# BLL-EBOOK.net
KiCad netlist of a schematic drawn in EAGLE
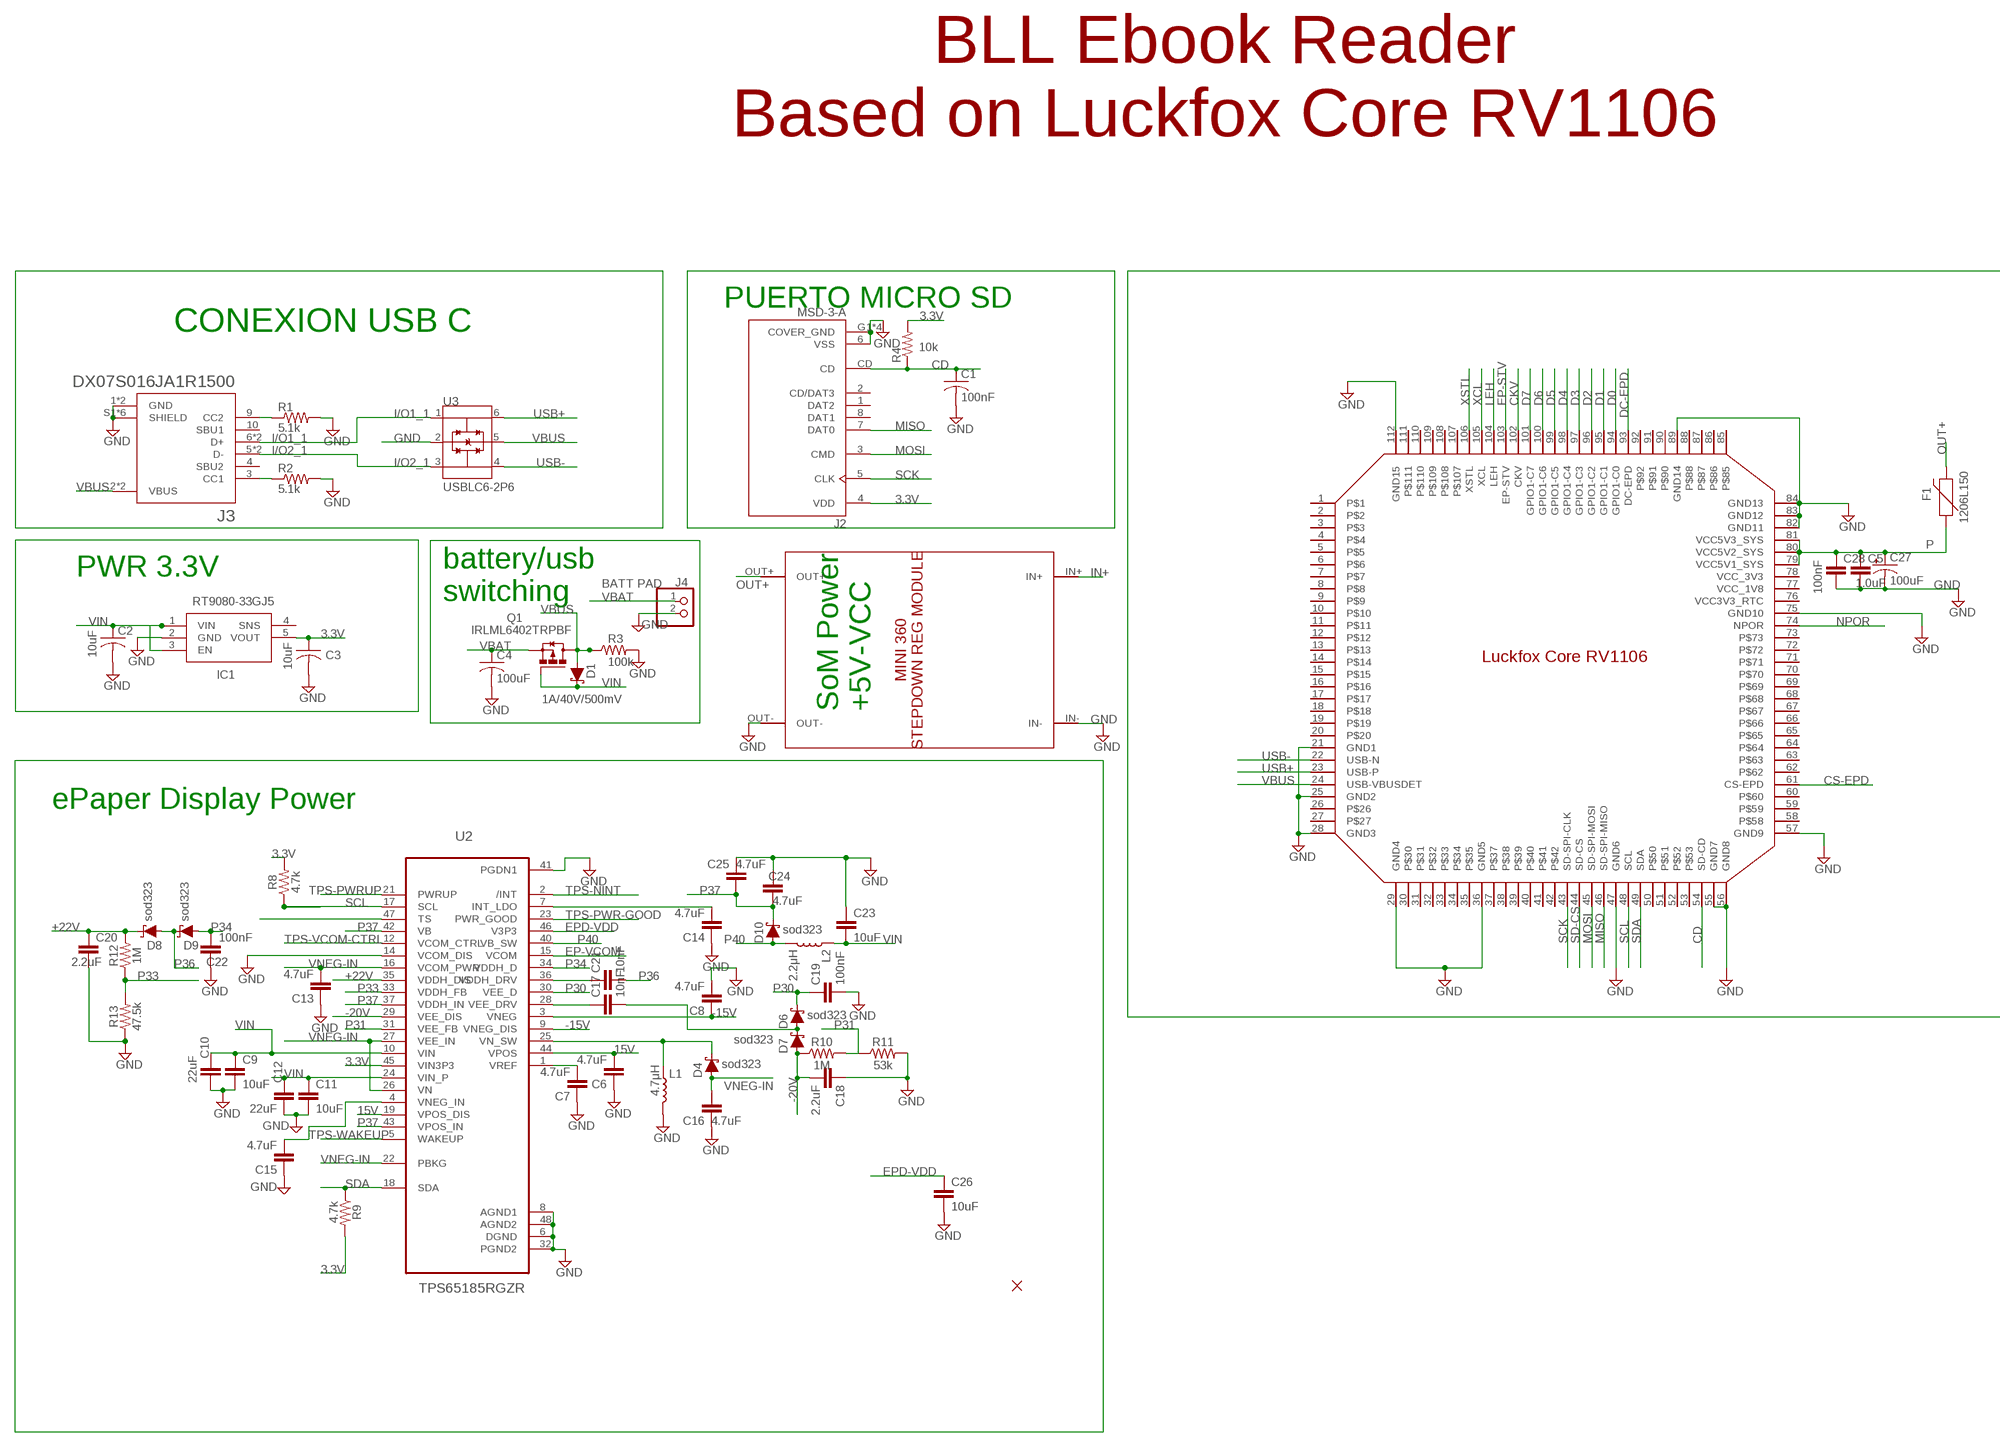
[diagram p0: schematic, sheet 1, part 1 of 2]
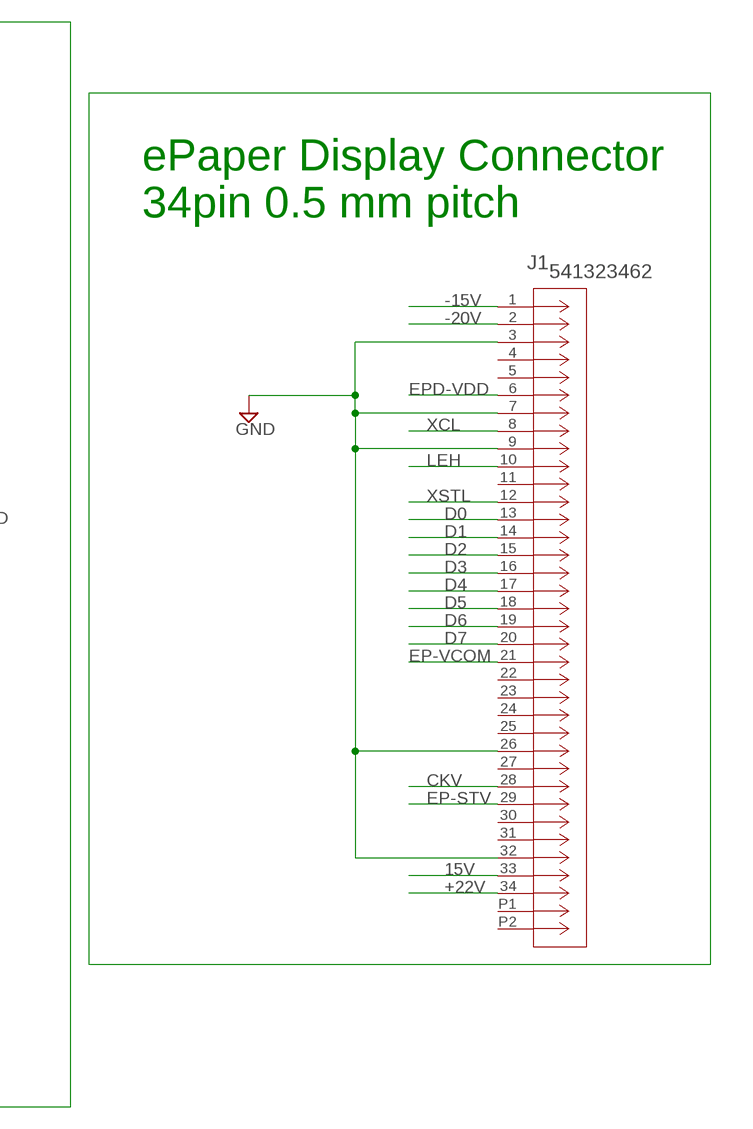
[diagram p1: schematic, sheet 1, part 2 of 2]

(export (version "E")
  (design (tool "Eeschema 10.0.6"))
  (components
    (comp (ref "C1")
      (value "100nF")
      (footprint "eagle-import:C0603")
      (libsource (lib "eagle-import") (part "C-USC0603"))
    )
    (comp (ref "C2")
      (value "10uF")
      (footprint "eagle-import:C0603")
      (libsource (lib "eagle-import") (part "C-USC0603"))
    )
    (comp (ref "C3")
      (value "10uF")
      (footprint "eagle-import:C0603")
      (libsource (lib "eagle-import") (part "C-USC0603"))
    )
    (comp (ref "C4")
      (value "100uF")
      (footprint "eagle-import:C0603")
      (libsource (lib "eagle-import") (part "C-USC0603"))
    )
    (comp (ref "C5")
      (value "1.0uF")
      (footprint "eagle-import:0603")
      (libsource (lib "eagle-import") (part "1.0UF-0603-16V-10%-X7R"))
    )
    (comp (ref "C6")
      (value "4.7uF")
      (footprint "eagle-import:0603")
      (libsource (lib "eagle-import") (part "4.7UF-0603-35V-(20%)"))
    )
    (comp (ref "C7")
      (value "4.7uF")
      (footprint "eagle-import:0603")
      (libsource (lib "eagle-import") (part "4.7UF-0603-35V-(20%)"))
    )
    (comp (ref "C8")
      (value "4.7uF")
      (footprint "eagle-import:0603")
      (libsource (lib "eagle-import") (part "4.7UF-0603-35V-(20%)"))
    )
    (comp (ref "C9")
      (value "10uF")
      (footprint "eagle-import:0805")
      (libsource (lib "eagle-import") (part "10UF-0805-10V-10%"))
    )
    (comp (ref "C10")
      (value "22uF")
      (footprint "eagle-import:0805")
      (libsource (lib "eagle-import") (part "22UF-0805-16V-20%"))
    )
    (comp (ref "C11")
      (value "10uF")
      (footprint "eagle-import:0805")
      (libsource (lib "eagle-import") (part "10UF-0805-10V-10%"))
    )
    (comp (ref "C12")
      (value "22uF")
      (footprint "eagle-import:0805")
      (libsource (lib "eagle-import") (part "22UF-0805-16V-20%"))
    )
    (comp (ref "C13")
      (value "4.7uF")
      (footprint "eagle-import:0603")
      (libsource (lib "eagle-import") (part "4.7UF-0603-35V-(20%)"))
    )
    (comp (ref "C14")
      (value "4.7uF")
      (footprint "eagle-import:0603")
      (libsource (lib "eagle-import") (part "4.7UF-0603-35V-(20%)"))
    )
    (comp (ref "C15")
      (value "4.7uF")
      (footprint "eagle-import:0603")
      (libsource (lib "eagle-import") (part "4.7UF-0603-35V-(20%)"))
    )
    (comp (ref "C16")
      (value "4.7uF")
      (footprint "eagle-import:0603")
      (libsource (lib "eagle-import") (part "4.7UF-0603-35V-(20%)"))
    )
    (comp (ref "C17")
      (value "10nF")
      (footprint "eagle-import:0603")
      (libsource (lib "eagle-import") (part "10NF-0603-50V-10%"))
    )
    (comp (ref "C18")
      (value "2.2uF")
      (footprint "eagle-import:1206")
      (libsource (lib "eagle-import") (part "2.2UF-1206-50V-10%"))
    )
    (comp (ref "C19")
      (value "100nF")
      (footprint "eagle-import:0603")
      (libsource (lib "eagle-import") (part "DNP-0603"))
    )
    (comp (ref "C20")
      (value "2.2uF")
      (footprint "eagle-import:1206")
      (libsource (lib "eagle-import") (part "2.2UF-1206-50V-10%"))
    )
    (comp (ref "C21")
      (value "10nF")
      (footprint "eagle-import:0603")
      (libsource (lib "eagle-import") (part "10NF-0603-50V-10%"))
    )
    (comp (ref "C22")
      (value "100nF")
      (footprint "eagle-import:0603")
      (libsource (lib "eagle-import") (part "DNP-0603"))
    )
    (comp (ref "C23")
      (value "10uF")
      (footprint "eagle-import:0805")
      (libsource (lib "eagle-import") (part "10UF-0805-10V-10%"))
    )
    (comp (ref "C24")
      (value "4.7uF")
      (footprint "eagle-import:0603")
      (libsource (lib "eagle-import") (part "4.7UF-0603-35V-(20%)"))
    )
    (comp (ref "C25")
      (value "4.7uF")
      (footprint "eagle-import:0603")
      (libsource (lib "eagle-import") (part "4.7UF-0603-35V-(20%)"))
    )
    (comp (ref "C26")
      (value "10uF")
      (footprint "eagle-import:0805")
      (libsource (lib "eagle-import") (part "10UF-0805-10V-10%"))
    )
    (comp (ref "C27")
      (value "100uF")
      (footprint "eagle-import:EIA3528")
      (libsource (lib "eagle-import") (part "100UF-POLAR-EIA3528-10V-20%(TANT)"))
    )
    (comp (ref "C28")
      (value "100nF")
      (footprint "eagle-import:0805")
      (libsource (lib "eagle-import") (part "CAP-0805"))
    )
    (comp (ref "D1")
      (value "1A/40V/500mV")
      (footprint "eagle-import:SMA-DIODE")
      (libsource (lib "eagle-import") (part "DIODE-SCHOTTKY-SS14"))
    )
    (comp (ref "D4")
      (value "sod323")
      (footprint "eagle-import:SOD-323")
      (libsource (lib "eagle-import") (part "DIODE-SCHOTTKY-PMEG4005EJ"))
    )
    (comp (ref "D6")
      (value "sod323")
      (footprint "eagle-import:SOD-323")
      (libsource (lib "eagle-import") (part "DIODE-SCHOTTKY-PMEG4005EJ"))
    )
    (comp (ref "D7")
      (value "sod323")
      (footprint "eagle-import:SOD-323")
      (libsource (lib "eagle-import") (part "DIODE-SCHOTTKY-PMEG4005EJ"))
    )
    (comp (ref "D8")
      (value "sod323")
      (footprint "eagle-import:SOD-323")
      (libsource (lib "eagle-import") (part "DIODE-SCHOTTKY-PMEG4005EJ"))
    )
    (comp (ref "D9")
      (value "sod323")
      (footprint "eagle-import:SOD-323")
      (libsource (lib "eagle-import") (part "DIODE-SCHOTTKY-PMEG4005EJ"))
    )
    (comp (ref "D10")
      (value "sod323")
      (footprint "eagle-import:SOD-323")
      (libsource (lib "eagle-import") (part "DIODE-SCHOTTKY-PMEG4005EJ"))
    )
    (comp (ref "F1")
      (value "1206L150")
      (footprint "eagle-import:1206")
      (libsource (lib "eagle-import") (part "PPTC_6V500MA-2"))
    )
    (comp (ref "IC1")
      (value "RT9080-33GJ5")
      (footprint "eagle-import:SOT94P280X100-5N")
      (fields (field (name "MF") "Richtek USA"))
      (libsource (lib "eagle-import") (part "RT9080-33GJ5"))
    )
    (comp (ref "J1")
      (value "541323462")
      (footprint "eagle-import:CON_541323462_MOL")
      (fields (field (name "MF") "Molex"))
      (libsource (lib "eagle-import") (part "541323462"))
    )
    (comp (ref "J2")
      (value "MSD-3-A")
      (footprint "eagle-import:CUI_MSD-3-A")
      (fields (field (name "MF") "Same Sky"))
      (libsource (lib "eagle-import") (part "MSD-3-A"))
    )
    (comp (ref "J3")
      (value "DX07S016JA1R1500")
      (footprint "eagle-import:JAE_DX07S016JA1R1500")
      (fields (field (name "MF") "JAE Electronics"))
      (libsource (lib "eagle-import") (part "DX07S016JA1R1500"))
    )
    (comp (ref "J4")
      (value "BATT PAD")
      (footprint "eagle-import:1X02_90")
      (libsource (lib "eagle-import") (part "PINHD-1X2/90"))
    )
    (comp (ref "L1")
      (value "4.7μH")
      (footprint "eagle-import:1008(2520)")
      (libsource (lib "eagle-import") (part "4.7μH_SHIELDED_INDUCTOR"))
    )
    (comp (ref "L2")
      (value "2.2μH")
      (footprint "eagle-import:0806")
      (libsource (lib "eagle-import") (part "2.2μH_SHIELDED_INDUCTOR"))
    )
    (comp (ref "Q1")
      (value "IRLML6402TRPBF")
      (footprint "eagle-import:SOT23")
      (fields (field (name "MF") "Infineon Technologies") (field (name "MP") "IRLML6402"))
      (libsource (lib "eagle-import") (part "IRLML6402TRPBF"))
    )
    (comp (ref "R1")
      (value "5.1k")
      (footprint "eagle-import:M0805")
      (libsource (lib "eagle-import") (part "R-US_M0805"))
    )
    (comp (ref "R2")
      (value "5.1k")
      (footprint "eagle-import:M0805")
      (libsource (lib "eagle-import") (part "R-US_M0805"))
    )
    (comp (ref "R3")
      (value "100k")
      (footprint "eagle-import:R0603")
      (libsource (lib "eagle-import") (part "R-US_R0603"))
    )
    (comp (ref "R4")
      (value "10k")
      (footprint "eagle-import:M0805")
      (libsource (lib "eagle-import") (part "R-US_M0805"))
    )
    (comp (ref "R8")
      (value "4.7k")
      (footprint "eagle-import:0603")
      (libsource (lib "eagle-import") (part "4.7KOHM-0603-1/10W-1%"))
    )
    (comp (ref "R9")
      (value "4.7k")
      (footprint "eagle-import:0603")
      (libsource (lib "eagle-import") (part "4.7KOHM-0603-1/10W-1%"))
    )
    (comp (ref "R10")
      (value "1M")
      (footprint "eagle-import:0603")
      (libsource (lib "eagle-import") (part "1MOHM-0603-1/4W-5%"))
    )
    (comp (ref "R11")
      (value "53k")
      (footprint "eagle-import:0805")
      (libsource (lib "eagle-import") (part "RESISTOR0805"))
    )
    (comp (ref "R12")
      (value "1M")
      (footprint "eagle-import:0603")
      (libsource (lib "eagle-import") (part "1MOHM-0603-1/4W-5%"))
    )
    (comp (ref "R13")
      (value "47.5k")
      (footprint "eagle-import:0805")
      (libsource (lib "eagle-import") (part "RESISTOR0805"))
    )
    (comp (ref "U$1")
      (value "LUCKFOX_CORE_RV1106")
      (footprint "eagle-import:CORE1106-SMT")
      (fields (field (name "MF") "Luckfox Systems") (field (name "MP") "LuckFox Core1106"))
      (libsource (lib "eagle-import") (part "LUCKFOX_CORE_RV1106"))
    )
    (comp (ref "U$2")
      (value "MINI360-MOD-REG")
      (footprint "eagle-import:MINI360")
      (libsource (lib "eagle-import") (part "MINI360-MOD-REG"))
    )
    (comp (ref "U2")
      (value "TPS65185RGZR")
      (footprint "eagle-import:QFN50P700X700X100-49N")
      (fields (field (name "MF") "Texas Instruments"))
      (libsource (lib "eagle-import") (part "TPS65185RGZR"))
    )
    (comp (ref "U3")
      (value "USBLC6-2P6")
      (footprint "eagle-import:SOT50P160X60-6N")
      (fields (field (name "MF") "STMicroelectronics"))
      (libsource (lib "eagle-import") (part "USBLC6-2P6"))
    )
  )
  (nets
    (net (code "1") (name "/+22V") (class "Default")
      (node (ref "C20") (pin "1") (pinfunction "1_1") (pintype "passive"))
      (node (ref "D8") (pin "C") (pinfunction "C_C") (pintype "passive"))
      (node (ref "J1") (pin "34") (pinfunction "34_34") (pintype "passive"))
      (node (ref "R12") (pin "2") (pinfunction "2_2") (pintype "passive"))
      (node (ref "U2") (pin "35") (pinfunction "VDDH_DIS_35") (pintype "input"))
    )
    (net (code "2") (name "/-15V") (class "Default")
      (node (ref "C8") (pin "1") (pinfunction "1_1") (pintype "passive"))
      (node (ref "J1") (pin "1") (pinfunction "1_1") (pintype "passive"))
      (node (ref "U2") (pin "3") (pinfunction "VNEG_3") (pintype "output"))
      (node (ref "U2") (pin "9") (pinfunction "VNEG_DIS_9") (pintype "output"))
    )
    (net (code "3") (name "/-20V") (class "Default")
      (node (ref "C18") (pin "2") (pinfunction "2_2") (pintype "passive"))
      (node (ref "D7") (pin "A") (pinfunction "A_A") (pintype "passive"))
      (node (ref "J1") (pin "2") (pinfunction "2_2") (pintype "passive"))
      (node (ref "R10") (pin "1") (pinfunction "1_1") (pintype "passive"))
      (node (ref "U2") (pin "29") (pinfunction "VEE_DIS_29") (pintype "input"))
    )
    (net (code "4") (name "/3.3V") (class "Default")
      (node (ref "C3") (pin "1") (pinfunction "1_1") (pintype "passive"))
      (node (ref "IC1") (pin "5") (pinfunction "VOUT_5") (pintype "bidirectional"))
      (node (ref "J2") (pin "4") (pinfunction "VDD_4") (pintype "power_in"))
      (node (ref "R4") (pin "2") (pinfunction "2_2") (pintype "passive"))
      (node (ref "R8") (pin "2") (pinfunction "2_2") (pintype "passive"))
      (node (ref "R9") (pin "2") (pinfunction "2_2") (pintype "passive"))
      (node (ref "U2") (pin "45") (pinfunction "VIN3P3_45") (pintype "input"))
    )
    (net (code "5") (name "/15V") (class "Default")
      (node (ref "C6") (pin "2") (pinfunction "2_2") (pintype "passive"))
      (node (ref "J1") (pin "33") (pinfunction "33_33") (pintype "passive"))
      (node (ref "U2") (pin "19") (pinfunction "VPOS_DIS_19") (pintype "input"))
      (node (ref "U2") (pin "44") (pinfunction "VPOS_44") (pintype "output"))
    )
    (net (code "6") (name "/CD") (class "Default")
      (node (ref "C1") (pin "1") (pinfunction "1_1") (pintype "passive"))
      (node (ref "J2") (pin "CD") (pinfunction "CD_CD") (pintype "passive"))
      (node (ref "R4") (pin "1") (pinfunction "1_1") (pintype "passive"))
      (node (ref "U$1") (pin "54") (pinfunction "SD-CD_54") (pintype "bidirectional"))
    )
    (net (code "7") (name "/CKV") (class "Default")
      (node (ref "J1") (pin "28") (pinfunction "28_28") (pintype "passive"))
      (node (ref "U$1") (pin "102") (pinfunction "CKV_102") (pintype "bidirectional"))
    )
    (net (code "8") (name "/CS-EPD") (class "Default")
      (node (ref "U$1") (pin "61") (pinfunction "CS-EPD_61") (pintype "bidirectional"))
    )
    (net (code "9") (name "/D0") (class "Default")
      (node (ref "J1") (pin "13") (pinfunction "13_13") (pintype "passive"))
      (node (ref "U$1") (pin "94") (pinfunction "GPIO1-C0_94") (pintype "bidirectional"))
    )
    (net (code "10") (name "/D1") (class "Default")
      (node (ref "J1") (pin "14") (pinfunction "14_14") (pintype "passive"))
      (node (ref "U$1") (pin "95") (pinfunction "GPIO1-C1_95") (pintype "bidirectional"))
    )
    (net (code "11") (name "/D2") (class "Default")
      (node (ref "J1") (pin "15") (pinfunction "15_15") (pintype "passive"))
      (node (ref "U$1") (pin "96") (pinfunction "GPIO1-C2_96") (pintype "bidirectional"))
    )
    (net (code "12") (name "/D3") (class "Default")
      (node (ref "J1") (pin "16") (pinfunction "16_16") (pintype "passive"))
      (node (ref "U$1") (pin "97") (pinfunction "GPIO1-C3_97") (pintype "bidirectional"))
    )
    (net (code "13") (name "/D4") (class "Default")
      (node (ref "J1") (pin "17") (pinfunction "17_17") (pintype "passive"))
      (node (ref "U$1") (pin "98") (pinfunction "GPIO1-C4_98") (pintype "bidirectional"))
    )
    (net (code "14") (name "/D5") (class "Default")
      (node (ref "J1") (pin "18") (pinfunction "18_18") (pintype "passive"))
      (node (ref "U$1") (pin "99") (pinfunction "GPIO1-C5_99") (pintype "bidirectional"))
    )
    (net (code "15") (name "/D6") (class "Default")
      (node (ref "J1") (pin "19") (pinfunction "19_19") (pintype "passive"))
      (node (ref "U$1") (pin "100") (pinfunction "GPIO1-C6_100") (pintype "bidirectional"))
    )
    (net (code "16") (name "/D7") (class "Default")
      (node (ref "J1") (pin "20") (pinfunction "20_20") (pintype "passive"))
      (node (ref "U$1") (pin "101") (pinfunction "GPIO1-C7_101") (pintype "bidirectional"))
    )
    (net (code "17") (name "/DC-EPD") (class "Default")
      (node (ref "U$1") (pin "93") (pinfunction "DC-EPD_93") (pintype "bidirectional"))
    )
    (net (code "18") (name "/EP-STV") (class "Default")
      (node (ref "J1") (pin "29") (pinfunction "29_29") (pintype "passive"))
      (node (ref "U$1") (pin "103") (pinfunction "EP-STV_103") (pintype "bidirectional"))
    )
    (net (code "19") (name "/EP-VCOM") (class "Default")
      (node (ref "J1") (pin "21") (pinfunction "21_21") (pintype "passive"))
      (node (ref "U2") (pin "15") (pinfunction "VCOM_15") (pintype "output"))
    )
    (net (code "20") (name "/EPD-VDD") (class "Default")
      (node (ref "C26") (pin "1") (pinfunction "1_1") (pintype "passive"))
      (node (ref "J1") (pin "6") (pinfunction "6_6") (pintype "passive"))
      (node (ref "U2") (pin "46") (pinfunction "V3P3_46") (pintype "output"))
    )
    (net (code "21") (name "/IN+") (class "Default")
      (node (ref "U$2") (pin "IN+") (pinfunction "IN+_IN+") (pintype "bidirectional"))
    )
    (net (code "22") (name "/I{slash}O1_1") (class "Default")
      (node (ref "J3") (pin "6") (pinfunction "D+_6") (pintype "passive"))
      (node (ref "J3") (pin "7") (pinfunction "D+_7") (pintype "passive"))
      (node (ref "U3") (pin "1") (pinfunction "I/O1_1_1") (pintype "bidirectional"))
    )
    (net (code "23") (name "/I{slash}O2_1") (class "Default")
      (node (ref "J3") (pin "5") (pinfunction "D-_5") (pintype "passive"))
      (node (ref "J3") (pin "8") (pinfunction "D-_8") (pintype "passive"))
      (node (ref "U3") (pin "3") (pinfunction "I/O2_1_3") (pintype "bidirectional"))
    )
    (net (code "24") (name "/LEH") (class "Default")
      (node (ref "J1") (pin "10") (pinfunction "10_10") (pintype "passive"))
      (node (ref "U$1") (pin "104") (pinfunction "LEH_104") (pintype "bidirectional"))
    )
    (net (code "25") (name "/MISO") (class "Default")
      (node (ref "J2") (pin "7") (pinfunction "DAT0_7") (pintype "bidirectional"))
      (node (ref "U$1") (pin "46") (pinfunction "SD-SPI-MISO_46") (pintype "bidirectional"))
    )
    (net (code "26") (name "/MOSI") (class "Default")
      (node (ref "J2") (pin "3") (pinfunction "CMD_3") (pintype "bidirectional"))
      (node (ref "U$1") (pin "45") (pinfunction "SD-SPI-MOSI_45") (pintype "bidirectional"))
    )
    (net (code "27") (name "/NPOR") (class "Default")
      (node (ref "U$1") (pin "74") (pinfunction "NPOR_74") (pintype "bidirectional"))
    )
    (net (code "28") (name "/OUT+") (class "Default")
      (node (ref "F1") (pin "2") (pinfunction "2_2") (pintype "bidirectional"))
      (node (ref "U$2") (pin "OUT+") (pinfunction "OUT+_OUT+") (pintype "bidirectional"))
    )
    (net (code "29") (name "/P") (class "Default")
      (node (ref "C27") (pin "A") (pinfunction "+_A") (pintype "passive"))
      (node (ref "C28") (pin "1") (pinfunction "1_1") (pintype "passive"))
      (node (ref "C5") (pin "1") (pinfunction "1_1") (pintype "passive"))
      (node (ref "F1") (pin "1") (pinfunction "1_1") (pintype "bidirectional"))
      (node (ref "U$1") (pin "79") (pinfunction "VCC5V1_SYS_79") (pintype "power_in"))
      (node (ref "U$1") (pin "80") (pinfunction "VCC5V2_SYS_80") (pintype "bidirectional"))
      (node (ref "U$1") (pin "81") (pinfunction "VCC5V3_SYS_81") (pintype "bidirectional"))
    )
    (net (code "30") (name "/P30") (class "Default")
      (node (ref "C19") (pin "1") (pinfunction "1_1") (pintype "passive"))
      (node (ref "D6") (pin "C") (pinfunction "C_C") (pintype "passive"))
      (node (ref "U2") (pin "30") (pinfunction "VEE_D_30") (pintype "output"))
    )
    (net (code "31") (name "/P31") (class "Default")
      (node (ref "R10") (pin "2") (pinfunction "2_2") (pintype "passive"))
      (node (ref "R11") (pin "1") (pinfunction "1_1") (pintype "passive"))
      (node (ref "U2") (pin "31") (pinfunction "VEE_FB_31") (pintype "input"))
    )
    (net (code "32") (name "/P33") (class "Default")
      (node (ref "R12") (pin "1") (pinfunction "1_1") (pintype "passive"))
      (node (ref "R13") (pin "2") (pinfunction "2_2") (pintype "passive"))
      (node (ref "U2") (pin "33") (pinfunction "VDDH_FB_33") (pintype "input"))
    )
    (net (code "33") (name "/P34") (class "Default")
      (node (ref "C22") (pin "2") (pinfunction "2_2") (pintype "passive"))
      (node (ref "D9") (pin "A") (pinfunction "A_A") (pintype "passive"))
      (node (ref "U2") (pin "34") (pinfunction "VDDH_D_34") (pintype "output"))
    )
    (net (code "34") (name "/P36") (class "Default")
      (node (ref "C21") (pin "2") (pinfunction "2_2") (pintype "passive"))
      (node (ref "D8") (pin "A") (pinfunction "A_A") (pintype "passive"))
      (node (ref "D9") (pin "C") (pinfunction "C_C") (pintype "passive"))
    )
    (net (code "35") (name "/P37") (class "Default")
      (node (ref "C24") (pin "1") (pinfunction "1_1") (pintype "passive"))
      (node (ref "C25") (pin "1") (pinfunction "1_1") (pintype "passive"))
      (node (ref "D10") (pin "C") (pinfunction "C_C") (pintype "passive"))
      (node (ref "U2") (pin "37") (pinfunction "VDDH_IN_37") (pintype "input"))
      (node (ref "U2") (pin "42") (pinfunction "VB_42") (pintype "input"))
      (node (ref "U2") (pin "43") (pinfunction "VPOS_IN_43") (pintype "input"))
    )
    (net (code "36") (name "/P40") (class "Default")
      (node (ref "D10") (pin "A") (pinfunction "A_A") (pintype "passive"))
      (node (ref "L2") (pin "2") (pinfunction "2_2") (pintype "passive"))
      (node (ref "U2") (pin "40") (pinfunction "VB_SW_40") (pintype "output"))
    )
    (net (code "37") (name "/SCK") (class "Default")
      (node (ref "J2") (pin "5") (pinfunction "CLK_5") (pintype "input"))
      (node (ref "U$1") (pin "43") (pinfunction "SD-SPI-CLK_43") (pintype "bidirectional"))
    )
    (net (code "38") (name "/SCL") (class "Default")
      (node (ref "R8") (pin "1") (pinfunction "1_1") (pintype "passive"))
      (node (ref "U$1") (pin "48") (pinfunction "SCL_48") (pintype "bidirectional"))
      (node (ref "U2") (pin "17") (pinfunction "SCL_17") (pintype "input"))
    )
    (net (code "39") (name "/SD-CS") (class "Default")
      (node (ref "U$1") (pin "44") (pinfunction "SD-CS_44") (pintype "bidirectional"))
    )
    (net (code "40") (name "/SDA") (class "Default")
      (node (ref "R9") (pin "1") (pinfunction "1_1") (pintype "passive"))
      (node (ref "U$1") (pin "49") (pinfunction "SDA_49") (pintype "bidirectional"))
      (node (ref "U2") (pin "18") (pinfunction "SDA_18") (pintype "bidirectional"))
    )
    (net (code "41") (name "/TPS-NINT") (class "Default")
      (node (ref "U2") (pin "2") (pinfunction "/INT_2") (pintype "output"))
    )
    (net (code "42") (name "/TPS-PWR-GOOD") (class "Default")
      (node (ref "U2") (pin "23") (pinfunction "PWR_GOOD_23") (pintype "output"))
    )
    (net (code "43") (name "/TPS-PWRUP") (class "Default")
      (node (ref "U2") (pin "21") (pinfunction "PWRUP_21") (pintype "input"))
    )
    (net (code "44") (name "/TPS-VCOM-CTRL") (class "Default")
      (node (ref "U2") (pin "12") (pinfunction "VCOM_CTRL_12") (pintype "input"))
    )
    (net (code "45") (name "/TPS-WAKEUP") (class "Default")
      (node (ref "U2") (pin "5") (pinfunction "WAKEUP_5") (pintype "input"))
    )
    (net (code "46") (name "/USB+") (class "Default")
      (node (ref "U$1") (pin "23") (pinfunction "USB-P_23") (pintype "bidirectional"))
      (node (ref "U3") (pin "6") (pinfunction "I/O1_2_6") (pintype "bidirectional"))
    )
    (net (code "47") (name "/USB-") (class "Default")
      (node (ref "U$1") (pin "22") (pinfunction "USB-N_22") (pintype "bidirectional"))
      (node (ref "U3") (pin "4") (pinfunction "I/O2_2_4") (pintype "bidirectional"))
    )
    (net (code "48") (name "/VBAT") (class "Default")
      (node (ref "C4") (pin "1") (pinfunction "1_1") (pintype "passive"))
      (node (ref "J4") (pin "1") (pinfunction "1_1") (pintype "passive"))
      (node (ref "Q1") (pin "2") (pinfunction "S_2") (pintype "passive"))
    )
    (net (code "49") (name "/VBUS") (class "Default")
      (node (ref "D1") (pin "A") (pinfunction "A_A") (pintype "passive"))
      (node (ref "J3") (pin "11") (pinfunction "VBUS_11") (pintype "power_in"))
      (node (ref "J3") (pin "2") (pinfunction "VBUS_2") (pintype "power_in"))
      (node (ref "Q1") (pin "3") (pinfunction "D_3") (pintype "passive"))
      (node (ref "R3") (pin "1") (pinfunction "1_1") (pintype "passive"))
      (node (ref "U$1") (pin "24") (pinfunction "USB-VBUSDET_24") (pintype "bidirectional"))
      (node (ref "U3") (pin "5") (pinfunction "VBUS_5") (pintype "power_in"))
    )
    (net (code "50") (name "/VCC3V3_RTC") (class "Default")
      (node (ref "U$1") (pin "76") (pinfunction "VCC3V3_RTC_76") (pintype "power_in"))
    )
    (net (code "51") (name "/VIN") (class "Default")
      (node (ref "C10") (pin "1") (pinfunction "1_1") (pintype "passive"))
      (node (ref "C11") (pin "1") (pinfunction "1_1") (pintype "passive"))
      (node (ref "C12") (pin "1") (pinfunction "1_1") (pintype "passive"))
      (node (ref "C2") (pin "1") (pinfunction "1_1") (pintype "passive"))
      (node (ref "C23") (pin "2") (pinfunction "2_2") (pintype "passive"))
      (node (ref "C9") (pin "1") (pinfunction "1_1") (pintype "passive"))
      (node (ref "D1") (pin "C") (pinfunction "C_C") (pintype "passive"))
      (node (ref "IC1") (pin "1") (pinfunction "VIN_1") (pintype "bidirectional"))
      (node (ref "IC1") (pin "3") (pinfunction "EN_3") (pintype "bidirectional"))
      (node (ref "L2") (pin "1") (pinfunction "1_1") (pintype "passive"))
      (node (ref "Q1") (pin "1") (pinfunction "G_1") (pintype "passive"))
      (node (ref "U2") (pin "10") (pinfunction "VIN_10") (pintype "input"))
      (node (ref "U2") (pin "24") (pinfunction "VIN_P_24") (pintype "input"))
    )
    (net (code "52") (name "/VNEG-IN") (class "Default")
      (node (ref "C13") (pin "2") (pinfunction "2_2") (pintype "passive"))
      (node (ref "C16") (pin "2") (pinfunction "2_2") (pintype "passive"))
      (node (ref "D4") (pin "A") (pinfunction "A_A") (pintype "passive"))
      (node (ref "U2") (pin "16") (pinfunction "VCOM_PWR_16") (pintype "input"))
      (node (ref "U2") (pin "22") (pinfunction "PBKG_22") (pintype "bidirectional"))
      (node (ref "U2") (pin "26") (pinfunction "VN_26") (pintype "input"))
      (node (ref "U2") (pin "27") (pinfunction "VEE_IN_27") (pintype "input"))
    )
    (net (code "53") (name "/XCL") (class "Default")
      (node (ref "J1") (pin "8") (pinfunction "8_8") (pintype "passive"))
      (node (ref "U$1") (pin "105") (pinfunction "XCL_105") (pintype "bidirectional"))
    )
    (net (code "54") (name "/XSTL") (class "Default")
      (node (ref "J1") (pin "12") (pinfunction "12_12") (pintype "passive"))
      (node (ref "U$1") (pin "106") (pinfunction "XSTL_106") (pintype "bidirectional"))
    )
    (net (code "55") (name "GND") (class "Default")
      (node (ref "C1") (pin "2") (pinfunction "2_2") (pintype "passive"))
      (node (ref "C10") (pin "2") (pinfunction "2_2") (pintype "passive"))
      (node (ref "C11") (pin "2") (pinfunction "2_2") (pintype "passive"))
      (node (ref "C12") (pin "2") (pinfunction "2_2") (pintype "passive"))
      (node (ref "C13") (pin "1") (pinfunction "1_1") (pintype "passive"))
      (node (ref "C14") (pin "1") (pinfunction "1_1") (pintype "passive"))
      (node (ref "C15") (pin "1") (pinfunction "1_1") (pintype "passive"))
      (node (ref "C16") (pin "1") (pinfunction "1_1") (pintype "passive"))
      (node (ref "C18") (pin "1") (pinfunction "1_1") (pintype "passive"))
      (node (ref "C19") (pin "2") (pinfunction "2_2") (pintype "passive"))
      (node (ref "C2") (pin "2") (pinfunction "2_2") (pintype "passive"))
      (node (ref "C20") (pin "2") (pinfunction "2_2") (pintype "passive"))
      (node (ref "C22") (pin "1") (pinfunction "1_1") (pintype "passive"))
      (node (ref "C23") (pin "1") (pinfunction "1_1") (pintype "passive"))
      (node (ref "C24") (pin "2") (pinfunction "2_2") (pintype "passive"))
      (node (ref "C25") (pin "2") (pinfunction "2_2") (pintype "passive"))
      (node (ref "C26") (pin "2") (pinfunction "2_2") (pintype "passive"))
      (node (ref "C27") (pin "C") (pinfunction "-_C") (pintype "passive"))
      (node (ref "C28") (pin "2") (pinfunction "2_2") (pintype "passive"))
      (node (ref "C3") (pin "2") (pinfunction "2_2") (pintype "passive"))
      (node (ref "C4") (pin "2") (pinfunction "2_2") (pintype "passive"))
      (node (ref "C5") (pin "2") (pinfunction "2_2") (pintype "passive"))
      (node (ref "C6") (pin "1") (pinfunction "1_1") (pintype "passive"))
      (node (ref "C7") (pin "1") (pinfunction "1_1") (pintype "passive"))
      (node (ref "C8") (pin "2") (pinfunction "2_2") (pintype "passive"))
      (node (ref "C9") (pin "2") (pinfunction "2_2") (pintype "passive"))
      (node (ref "IC1") (pin "2") (pinfunction "GND_2") (pintype "bidirectional"))
      (node (ref "J1") (pin "26") (pinfunction "26_26") (pintype "passive"))
      (node (ref "J1") (pin "3") (pinfunction "3_3") (pintype "passive"))
      (node (ref "J1") (pin "32") (pinfunction "32_32") (pintype "passive"))
      (node (ref "J1") (pin "7") (pinfunction "7_7") (pintype "passive"))
      (node (ref "J1") (pin "9") (pinfunction "9_9") (pintype "passive"))
      (node (ref "J2") (pin "6") (pinfunction "VSS_6") (pintype "power_in"))
      (node (ref "J2") (pin "G1") (pinfunction "COVER_GND_G1") (pintype "power_in"))
      (node (ref "J2") (pin "G2") (pinfunction "COVER_GND_G2") (pintype "power_in"))
      (node (ref "J2") (pin "G3") (pinfunction "COVER_GND_G3") (pintype "power_in"))
      (node (ref "J2") (pin "G4") (pinfunction "COVER_GND_G4") (pintype "power_in"))
      (node (ref "J3") (pin "1") (pinfunction "GND_1") (pintype "power_in"))
      (node (ref "J3") (pin "12") (pinfunction "GND_12") (pintype "power_in"))
      (node (ref "J3") (pin "S1") (pinfunction "SHIELD_S1") (pintype "passive"))
      (node (ref "J3") (pin "S2") (pinfunction "SHIELD_S2") (pintype "passive"))
      (node (ref "J3") (pin "S3") (pinfunction "SHIELD_S3") (pintype "passive"))
      (node (ref "J3") (pin "S4") (pinfunction "SHIELD_S4") (pintype "passive"))
      (node (ref "J3") (pin "S5") (pinfunction "SHIELD_S5") (pintype "passive"))
      (node (ref "J3") (pin "S6") (pinfunction "SHIELD_S6") (pintype "passive"))
      (node (ref "J4") (pin "2") (pinfunction "2_2") (pintype "passive"))
      (node (ref "L1") (pin "2") (pinfunction "2_2") (pintype "passive"))
      (node (ref "R1") (pin "2") (pinfunction "2_2") (pintype "passive"))
      (node (ref "R11") (pin "2") (pinfunction "2_2") (pintype "passive"))
      (node (ref "R13") (pin "1") (pinfunction "1_1") (pintype "passive"))
      (node (ref "R2") (pin "2") (pinfunction "2_2") (pintype "passive"))
      (node (ref "R3") (pin "2") (pinfunction "2_2") (pintype "passive"))
      (node (ref "U$1") (pin "112") (pinfunction "GND15_112") (pintype "bidirectional"))
      (node (ref "U$1") (pin "21") (pinfunction "GND1_21") (pintype "bidirectional"))
      (node (ref "U$1") (pin "25") (pinfunction "GND2_25") (pintype "output"))
      (node (ref "U$1") (pin "28") (pinfunction "GND3_28") (pintype "bidirectional"))
      (node (ref "U$1") (pin "29") (pinfunction "GND4_29") (pintype "bidirectional"))
      (node (ref "U$1") (pin "36") (pinfunction "GND5_36") (pintype "bidirectional"))
      (node (ref "U$1") (pin "47") (pinfunction "GND6_47") (pintype "bidirectional"))
      (node (ref "U$1") (pin "55") (pinfunction "GND7_55") (pintype "bidirectional"))
      (node (ref "U$1") (pin "56") (pinfunction "GND8_56") (pintype "bidirectional"))
      (node (ref "U$1") (pin "57") (pinfunction "GND9_57") (pintype "bidirectional"))
      (node (ref "U$1") (pin "75") (pinfunction "GND10_75") (pintype "bidirectional"))
      (node (ref "U$1") (pin "82") (pinfunction "GND11_82") (pintype "bidirectional"))
      (node (ref "U$1") (pin "83") (pinfunction "GND12_83") (pintype "bidirectional"))
      (node (ref "U$1") (pin "84") (pinfunction "GND13_84") (pintype "bidirectional"))
      (node (ref "U$1") (pin "89") (pinfunction "GND14_89") (pintype "bidirectional"))
      (node (ref "U$2") (pin "IN-") (pinfunction "IN-_IN-") (pintype "bidirectional"))
      (node (ref "U$2") (pin "OUT-") (pinfunction "OUT-_OUT-") (pintype "bidirectional"))
      (node (ref "U2") (pin "14") (pinfunction "VCOM_DIS_14") (pintype "input"))
      (node (ref "U2") (pin "32") (pinfunction "PGND2_32") (pintype "power_in"))
      (node (ref "U2") (pin "41") (pinfunction "PGDN1_41") (pintype "power_in"))
      (node (ref "U2") (pin "48") (pinfunction "AGND2_48") (pintype "power_in"))
      (node (ref "U2") (pin "6") (pinfunction "DGND_6") (pintype "power_in"))
      (node (ref "U2") (pin "8") (pinfunction "AGND1_8") (pintype "power_in"))
      (node (ref "U3") (pin "2") (pinfunction "GND_2") (pintype "power_in"))
    )
    (net (code "56") (name "Net-(C17-Pad2)") (class "Default")
      (node (ref "C17") (pin "2") (pinfunction "2_2") (pintype "passive"))
      (node (ref "D6") (pin "A") (pinfunction "A_A") (pintype "passive"))
      (node (ref "D7") (pin "C") (pinfunction "C_C") (pintype "passive"))
    )
    (net (code "57") (name "Net-(J3-CC1)") (class "Default")
      (node (ref "J3") (pin "3") (pinfunction "CC1_3") (pintype "passive"))
      (node (ref "R2") (pin "1") (pinfunction "1_1") (pintype "passive"))
    )
    (net (code "58") (name "Net-(J3-CC2)") (class "Default")
      (node (ref "J3") (pin "9") (pinfunction "CC2_9") (pintype "passive"))
      (node (ref "R1") (pin "1") (pinfunction "1_1") (pintype "passive"))
    )
    (net (code "59") (name "Net-(U2-INT_LDO)") (class "Default")
      (node (ref "C14") (pin "2") (pinfunction "2_2") (pintype "passive"))
      (node (ref "U2") (pin "7") (pinfunction "INT_LDO_7") (pintype "output"))
    )
    (net (code "60") (name "Net-(U2-VDDH_DRV)") (class "Default")
      (node (ref "C21") (pin "1") (pinfunction "1_1") (pintype "passive"))
      (node (ref "U2") (pin "36") (pinfunction "VDDH_DRV_36") (pintype "output"))
    )
    (net (code "61") (name "Net-(U2-VEE_DRV)") (class "Default")
      (node (ref "C17") (pin "1") (pinfunction "1_1") (pintype "passive"))
      (node (ref "U2") (pin "28") (pinfunction "VEE_DRV_28") (pintype "output"))
    )
    (net (code "62") (name "Net-(U2-VNEG_IN)") (class "Default")
      (node (ref "C15") (pin "2") (pinfunction "2_2") (pintype "passive"))
      (node (ref "U2") (pin "4") (pinfunction "VNEG_IN_4") (pintype "input"))
    )
    (net (code "63") (name "Net-(U2-VN_SW)") (class "Default")
      (node (ref "D4") (pin "C") (pinfunction "C_C") (pintype "passive"))
      (node (ref "L1") (pin "1") (pinfunction "1_1") (pintype "passive"))
      (node (ref "U2") (pin "25") (pinfunction "VN_SW_25") (pintype "output"))
    )
    (net (code "64") (name "Net-(U2-VREF)") (class "Default")
      (node (ref "C7") (pin "2") (pinfunction "2_2") (pintype "passive"))
      (node (ref "U2") (pin "1") (pinfunction "VREF_1") (pintype "output"))
    )
    (net (code "65") (name "unconnected-(IC1-SNS-Pad4)") (class "Default")
      (node (ref "IC1") (pin "4") (pinfunction "SNS_4") (pintype "bidirectional"))
    )
    (net (code "66") (name "unconnected-(J1-Pad4)") (class "Default")
      (node (ref "J1") (pin "4") (pinfunction "4_4") (pintype "passive"))
    )
    (net (code "67") (name "unconnected-(J1-Pad5)") (class "Default")
      (node (ref "J1") (pin "5") (pinfunction "5_5") (pintype "passive"))
    )
    (net (code "68") (name "unconnected-(J1-Pad11)") (class "Default")
      (node (ref "J1") (pin "11") (pinfunction "11_11") (pintype "passive"))
    )
    (net (code "69") (name "unconnected-(J1-Pad22)") (class "Default")
      (node (ref "J1") (pin "22") (pinfunction "22_22") (pintype "passive"))
    )
    (net (code "70") (name "unconnected-(J1-Pad23)") (class "Default")
      (node (ref "J1") (pin "23") (pinfunction "23_23") (pintype "passive"))
    )
    (net (code "71") (name "unconnected-(J1-Pad24)") (class "Default")
      (node (ref "J1") (pin "24") (pinfunction "24_24") (pintype "passive"))
    )
    (net (code "72") (name "unconnected-(J1-Pad25)") (class "Default")
      (node (ref "J1") (pin "25") (pinfunction "25_25") (pintype "passive"))
    )
    (net (code "73") (name "unconnected-(J1-Pad27)") (class "Default")
      (node (ref "J1") (pin "27") (pinfunction "27_27") (pintype "passive"))
    )
    (net (code "74") (name "unconnected-(J1-Pad30)") (class "Default")
      (node (ref "J1") (pin "30") (pinfunction "30_30") (pintype "passive"))
    )
    (net (code "75") (name "unconnected-(J1-Pad31)") (class "Default")
      (node (ref "J1") (pin "31") (pinfunction "31_31") (pintype "passive"))
    )
    (net (code "76") (name "unconnected-(J1-PadP1)") (class "Default")
      (node (ref "J1") (pin "P1") (pinfunction "P1_P1") (pintype "passive"))
    )
    (net (code "77") (name "unconnected-(J1-PadP2)") (class "Default")
      (node (ref "J1") (pin "P2") (pinfunction "P2_P2") (pintype "passive"))
    )
    (net (code "78") (name "unconnected-(J2-CD{slash}DAT3-Pad2)") (class "Default")
      (node (ref "J2") (pin "2") (pinfunction "CD/DAT3_2") (pintype "bidirectional"))
    )
    (net (code "79") (name "unconnected-(J2-DAT1-Pad8)") (class "Default")
      (node (ref "J2") (pin "8") (pinfunction "DAT1_8") (pintype "bidirectional"))
    )
    (net (code "80") (name "unconnected-(J2-DAT2-Pad1)") (class "Default")
      (node (ref "J2") (pin "1") (pinfunction "DAT2_1") (pintype "bidirectional"))
    )
    (net (code "81") (name "unconnected-(J3-SBU1-Pad10)") (class "Default")
      (node (ref "J3") (pin "10") (pinfunction "SBU1_10") (pintype "passive"))
    )
    (net (code "82") (name "unconnected-(J3-SBU2-Pad4)") (class "Default")
      (node (ref "J3") (pin "4") (pinfunction "SBU2_4") (pintype "passive"))
    )
    (net (code "83") (name "unconnected-(U$1-P$1-Pad1)") (class "Default")
      (node (ref "U$1") (pin "1") (pinfunction "P$1_1") (pintype "bidirectional"))
    )
    (net (code "84") (name "unconnected-(U$1-P$2-Pad2)") (class "Default")
      (node (ref "U$1") (pin "2") (pinfunction "P$2_2") (pintype "bidirectional"))
    )
    (net (code "85") (name "unconnected-(U$1-P$3-Pad3)") (class "Default")
      (node (ref "U$1") (pin "3") (pinfunction "P$3_3") (pintype "bidirectional"))
    )
    (net (code "86") (name "unconnected-(U$1-P$4-Pad4)") (class "Default")
      (node (ref "U$1") (pin "4") (pinfunction "P$4_4") (pintype "bidirectional"))
    )
    (net (code "87") (name "unconnected-(U$1-P$5-Pad5)") (class "Default")
      (node (ref "U$1") (pin "5") (pinfunction "P$5_5") (pintype "bidirectional"))
    )
    (net (code "88") (name "unconnected-(U$1-P$6-Pad6)") (class "Default")
      (node (ref "U$1") (pin "6") (pinfunction "P$6_6") (pintype "bidirectional"))
    )
    (net (code "89") (name "unconnected-(U$1-P$7-Pad7)") (class "Default")
      (node (ref "U$1") (pin "7") (pinfunction "P$7_7") (pintype "bidirectional"))
    )
    (net (code "90") (name "unconnected-(U$1-P$8-Pad8)") (class "Default")
      (node (ref "U$1") (pin "8") (pinfunction "P$8_8") (pintype "bidirectional"))
    )
    (net (code "91") (name "unconnected-(U$1-P$9-Pad9)") (class "Default")
      (node (ref "U$1") (pin "9") (pinfunction "P$9_9") (pintype "bidirectional"))
    )
    (net (code "92") (name "unconnected-(U$1-P$10-Pad10)") (class "Default")
      (node (ref "U$1") (pin "10") (pinfunction "P$10_10") (pintype "bidirectional"))
    )
    (net (code "93") (name "unconnected-(U$1-P$11-Pad11)") (class "Default")
      (node (ref "U$1") (pin "11") (pinfunction "P$11_11") (pintype "bidirectional"))
    )
    (net (code "94") (name "unconnected-(U$1-P$12-Pad12)") (class "Default")
      (node (ref "U$1") (pin "12") (pinfunction "P$12_12") (pintype "bidirectional"))
    )
    (net (code "95") (name "unconnected-(U$1-P$13-Pad13)") (class "Default")
      (node (ref "U$1") (pin "13") (pinfunction "P$13_13") (pintype "bidirectional"))
    )
    (net (code "96") (name "unconnected-(U$1-P$14-Pad14)") (class "Default")
      (node (ref "U$1") (pin "14") (pinfunction "P$14_14") (pintype "bidirectional"))
    )
    (net (code "97") (name "unconnected-(U$1-P$15-Pad15)") (class "Default")
      (node (ref "U$1") (pin "15") (pinfunction "P$15_15") (pintype "bidirectional"))
    )
    (net (code "98") (name "unconnected-(U$1-P$16-Pad16)") (class "Default")
      (node (ref "U$1") (pin "16") (pinfunction "P$16_16") (pintype "bidirectional"))
    )
    (net (code "99") (name "unconnected-(U$1-P$17-Pad17)") (class "Default")
      (node (ref "U$1") (pin "17") (pinfunction "P$17_17") (pintype "bidirectional"))
    )
    (net (code "100") (name "unconnected-(U$1-P$18-Pad18)") (class "Default")
      (node (ref "U$1") (pin "18") (pinfunction "P$18_18") (pintype "bidirectional"))
    )
    (net (code "101") (name "unconnected-(U$1-P$19-Pad19)") (class "Default")
      (node (ref "U$1") (pin "19") (pinfunction "P$19_19") (pintype "bidirectional"))
    )
    (net (code "102") (name "unconnected-(U$1-P$20-Pad20)") (class "Default")
      (node (ref "U$1") (pin "20") (pinfunction "P$20_20") (pintype "bidirectional"))
    )
    (net (code "103") (name "unconnected-(U$1-P$26-Pad26)") (class "Default")
      (node (ref "U$1") (pin "26") (pinfunction "P$26_26") (pintype "bidirectional"))
    )
    (net (code "104") (name "unconnected-(U$1-P$27-Pad27)") (class "Default")
      (node (ref "U$1") (pin "27") (pinfunction "P$27_27") (pintype "bidirectional"))
    )
    (net (code "105") (name "unconnected-(U$1-P$30-Pad30)") (class "Default")
      (node (ref "U$1") (pin "30") (pinfunction "P$30_30") (pintype "bidirectional"))
    )
    (net (code "106") (name "unconnected-(U$1-P$31-Pad31)") (class "Default")
      (node (ref "U$1") (pin "31") (pinfunction "P$31_31") (pintype "bidirectional"))
    )
    (net (code "107") (name "unconnected-(U$1-P$32-Pad32)") (class "Default")
      (node (ref "U$1") (pin "32") (pinfunction "P$32_32") (pintype "bidirectional"))
    )
    (net (code "108") (name "unconnected-(U$1-P$33-Pad33)") (class "Default")
      (node (ref "U$1") (pin "33") (pinfunction "P$33_33") (pintype "bidirectional"))
    )
    (net (code "109") (name "unconnected-(U$1-P$34-Pad34)") (class "Default")
      (node (ref "U$1") (pin "34") (pinfunction "P$34_34") (pintype "bidirectional"))
    )
    (net (code "110") (name "unconnected-(U$1-P$35-Pad35)") (class "Default")
      (node (ref "U$1") (pin "35") (pinfunction "P$35_35") (pintype "bidirectional"))
    )
    (net (code "111") (name "unconnected-(U$1-P$37-Pad37)") (class "Default")
      (node (ref "U$1") (pin "37") (pinfunction "P$37_37") (pintype "bidirectional"))
    )
    (net (code "112") (name "unconnected-(U$1-P$38-Pad38)") (class "Default")
      (node (ref "U$1") (pin "38") (pinfunction "P$38_38") (pintype "bidirectional"))
    )
    (net (code "113") (name "unconnected-(U$1-P$39-Pad39)") (class "Default")
      (node (ref "U$1") (pin "39") (pinfunction "P$39_39") (pintype "bidirectional"))
    )
    (net (code "114") (name "unconnected-(U$1-P$40-Pad40)") (class "Default")
      (node (ref "U$1") (pin "40") (pinfunction "P$40_40") (pintype "bidirectional"))
    )
    (net (code "115") (name "unconnected-(U$1-P$41-Pad41)") (class "Default")
      (node (ref "U$1") (pin "41") (pinfunction "P$41_41") (pintype "bidirectional"))
    )
    (net (code "116") (name "unconnected-(U$1-P$42-Pad42)") (class "Default")
      (node (ref "U$1") (pin "42") (pinfunction "P$42_42") (pintype "bidirectional"))
    )
    (net (code "117") (name "unconnected-(U$1-P$50-Pad50)") (class "Default")
      (node (ref "U$1") (pin "50") (pinfunction "P$50_50") (pintype "bidirectional"))
    )
    (net (code "118") (name "unconnected-(U$1-P$51-Pad51)") (class "Default")
      (node (ref "U$1") (pin "51") (pinfunction "P$51_51") (pintype "bidirectional"))
    )
    (net (code "119") (name "unconnected-(U$1-P$52-Pad52)") (class "Default")
      (node (ref "U$1") (pin "52") (pinfunction "P$52_52") (pintype "bidirectional"))
    )
    (net (code "120") (name "unconnected-(U$1-P$53-Pad53)") (class "Default")
      (node (ref "U$1") (pin "53") (pinfunction "P$53_53") (pintype "bidirectional"))
    )
    (net (code "121") (name "unconnected-(U$1-P$58-Pad58)") (class "Default")
      (node (ref "U$1") (pin "58") (pinfunction "P$58_58") (pintype "bidirectional"))
    )
    (net (code "122") (name "unconnected-(U$1-P$59-Pad59)") (class "Default")
      (node (ref "U$1") (pin "59") (pinfunction "P$59_59") (pintype "bidirectional"))
    )
    (net (code "123") (name "unconnected-(U$1-P$60-Pad60)") (class "Default")
      (node (ref "U$1") (pin "60") (pinfunction "P$60_60") (pintype "bidirectional"))
    )
    (net (code "124") (name "unconnected-(U$1-P$62-Pad62)") (class "Default")
      (node (ref "U$1") (pin "62") (pinfunction "P$62_62") (pintype "bidirectional"))
    )
    (net (code "125") (name "unconnected-(U$1-P$63-Pad63)") (class "Default")
      (node (ref "U$1") (pin "63") (pinfunction "P$63_63") (pintype "bidirectional"))
    )
    (net (code "126") (name "unconnected-(U$1-P$64-Pad64)") (class "Default")
      (node (ref "U$1") (pin "64") (pinfunction "P$64_64") (pintype "bidirectional"))
    )
    (net (code "127") (name "unconnected-(U$1-P$65-Pad65)") (class "Default")
      (node (ref "U$1") (pin "65") (pinfunction "P$65_65") (pintype "bidirectional"))
    )
    (net (code "128") (name "unconnected-(U$1-P$66-Pad66)") (class "Default")
      (node (ref "U$1") (pin "66") (pinfunction "P$66_66") (pintype "bidirectional"))
    )
    (net (code "129") (name "unconnected-(U$1-P$67-Pad67)") (class "Default")
      (node (ref "U$1") (pin "67") (pinfunction "P$67_67") (pintype "bidirectional"))
    )
    (net (code "130") (name "unconnected-(U$1-P$68-Pad68)") (class "Default")
      (node (ref "U$1") (pin "68") (pinfunction "P$68_68") (pintype "bidirectional"))
    )
    (net (code "131") (name "unconnected-(U$1-P$69-Pad69)") (class "Default")
      (node (ref "U$1") (pin "69") (pinfunction "P$69_69") (pintype "bidirectional"))
    )
    (net (code "132") (name "unconnected-(U$1-P$70-Pad70)") (class "Default")
      (node (ref "U$1") (pin "70") (pinfunction "P$70_70") (pintype "bidirectional"))
    )
    (net (code "133") (name "unconnected-(U$1-P$71-Pad71)") (class "Default")
      (node (ref "U$1") (pin "71") (pinfunction "P$71_71") (pintype "bidirectional"))
    )
    (net (code "134") (name "unconnected-(U$1-P$72-Pad72)") (class "Default")
      (node (ref "U$1") (pin "72") (pinfunction "P$72_72") (pintype "bidirectional"))
    )
    (net (code "135") (name "unconnected-(U$1-P$73-Pad73)") (class "Default")
      (node (ref "U$1") (pin "73") (pinfunction "P$73_73") (pintype "bidirectional"))
    )
    (net (code "136") (name "unconnected-(U$1-P$85-Pad85)") (class "Default")
      (node (ref "U$1") (pin "85") (pinfunction "P$85_85") (pintype "bidirectional"))
    )
    (net (code "137") (name "unconnected-(U$1-P$86-Pad86)") (class "Default")
      (node (ref "U$1") (pin "86") (pinfunction "P$86_86") (pintype "bidirectional"))
    )
    (net (code "138") (name "unconnected-(U$1-P$87-Pad87)") (class "Default")
      (node (ref "U$1") (pin "87") (pinfunction "P$87_87") (pintype "bidirectional"))
    )
    (net (code "139") (name "unconnected-(U$1-P$88-Pad88)") (class "Default")
      (node (ref "U$1") (pin "88") (pinfunction "P$88_88") (pintype "bidirectional"))
    )
    (net (code "140") (name "unconnected-(U$1-P$90-Pad90)") (class "Default")
      (node (ref "U$1") (pin "90") (pinfunction "P$90_90") (pintype "bidirectional"))
    )
    (net (code "141") (name "unconnected-(U$1-P$91-Pad91)") (class "Default")
      (node (ref "U$1") (pin "91") (pinfunction "P$91_91") (pintype "bidirectional"))
    )
    (net (code "142") (name "unconnected-(U$1-P$92-Pad92)") (class "Default")
      (node (ref "U$1") (pin "92") (pinfunction "P$92_92") (pintype "bidirectional"))
    )
    (net (code "143") (name "unconnected-(U$1-P$107-Pad107)") (class "Default")
      (node (ref "U$1") (pin "107") (pinfunction "P$107_107") (pintype "bidirectional"))
    )
    (net (code "144") (name "unconnected-(U$1-P$108-Pad108)") (class "Default")
      (node (ref "U$1") (pin "108") (pinfunction "P$108_108") (pintype "bidirectional"))
    )
    (net (code "145") (name "unconnected-(U$1-P$109-Pad109)") (class "Default")
      (node (ref "U$1") (pin "109") (pinfunction "P$109_109") (pintype "bidirectional"))
    )
    (net (code "146") (name "unconnected-(U$1-P$110-Pad110)") (class "Default")
      (node (ref "U$1") (pin "110") (pinfunction "P$110_110") (pintype "bidirectional"))
    )
    (net (code "147") (name "unconnected-(U$1-P$111-Pad111)") (class "Default")
      (node (ref "U$1") (pin "111") (pinfunction "P$111_111") (pintype "bidirectional"))
    )
    (net (code "148") (name "unconnected-(U$1-VCC_1V8-Pad77)") (class "Default")
      (node (ref "U$1") (pin "77") (pinfunction "VCC_1V8_77") (pintype "output"))
    )
    (net (code "149") (name "unconnected-(U$1-VCC_3V3-Pad78)") (class "Default")
      (node (ref "U$1") (pin "78") (pinfunction "VCC_3V3_78") (pintype "output"))
    )
    (net (code "150") (name "unconnected-(U2-TS-Pad47)") (class "Default")
      (node (ref "U2") (pin "47") (pinfunction "TS_47") (pintype "input"))
    )
  )
)
